# MSSRP-Temperature_System_beta_lite_2laye.net
KiCad netlist of a schematic drawn in EAGLE
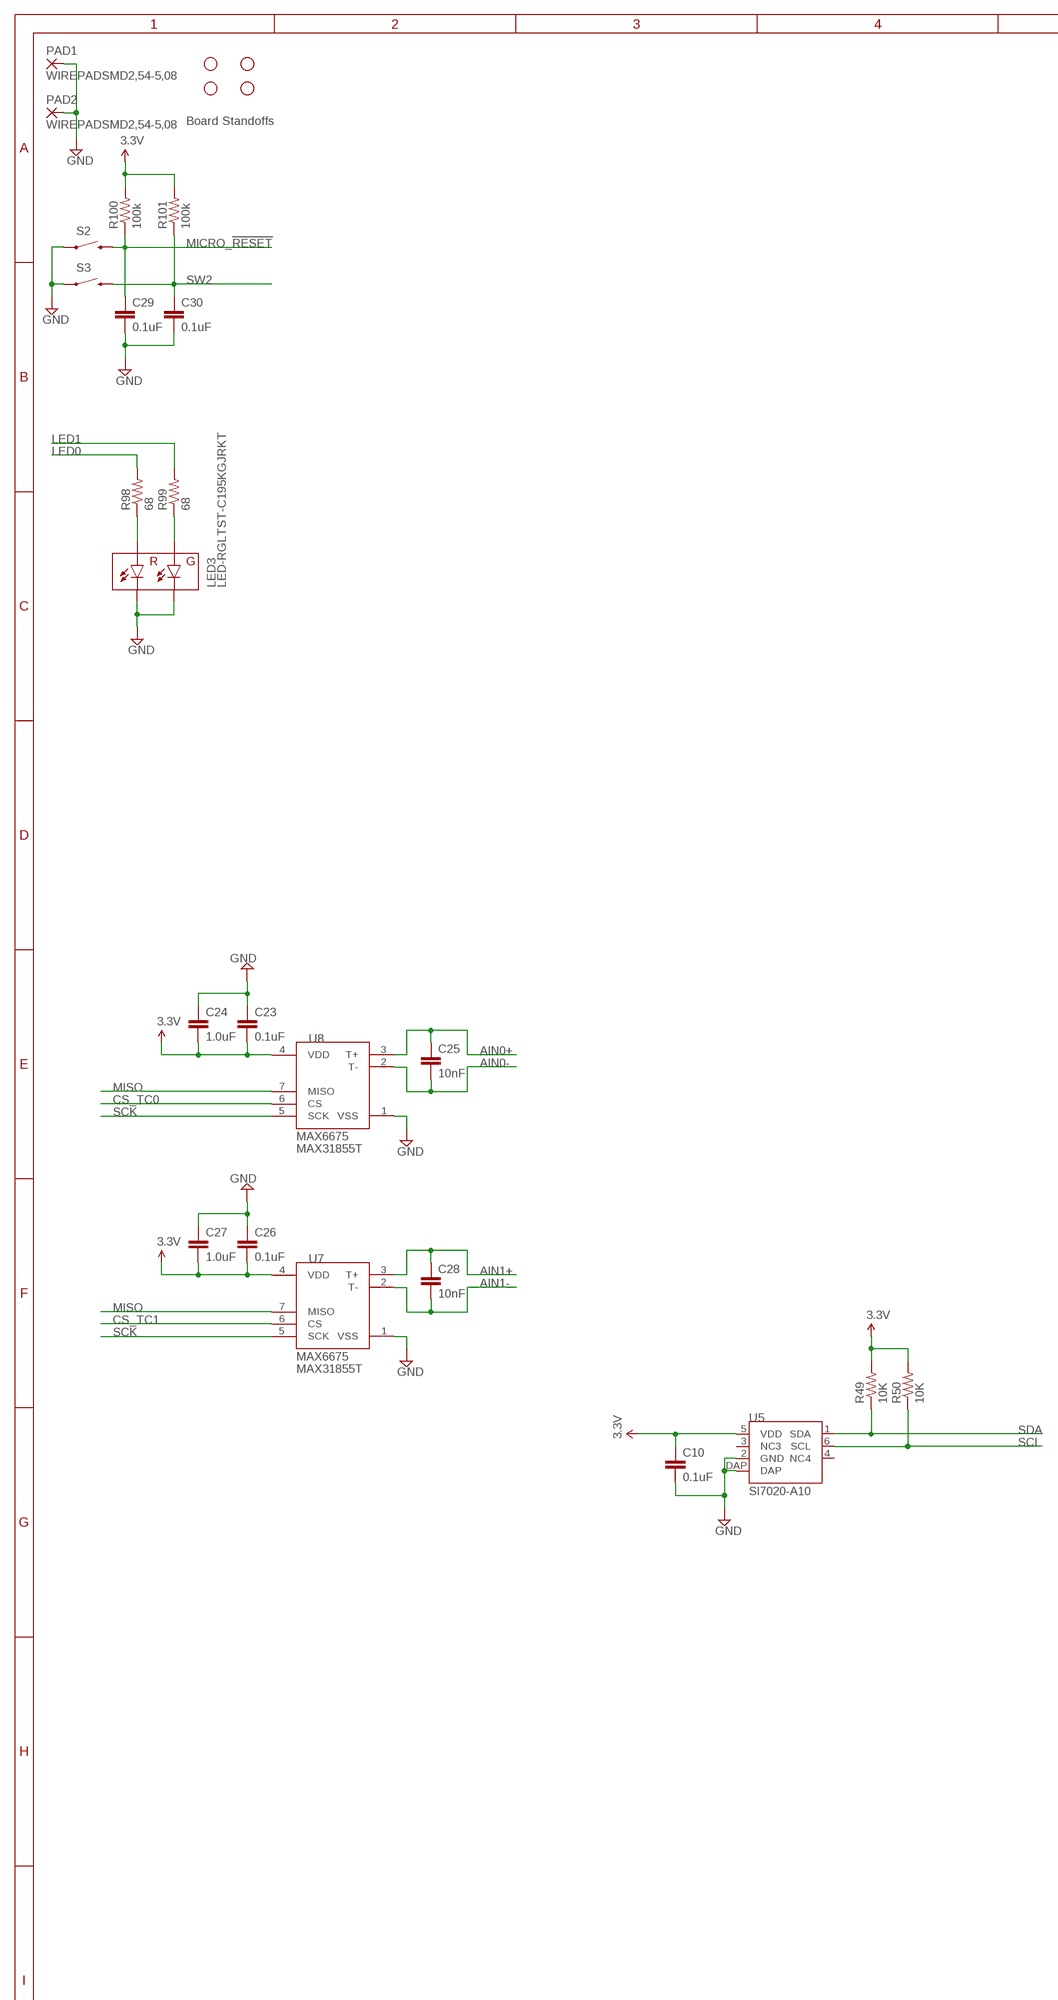
[diagram p0: schematic, sheet 1, part 1 of 2]
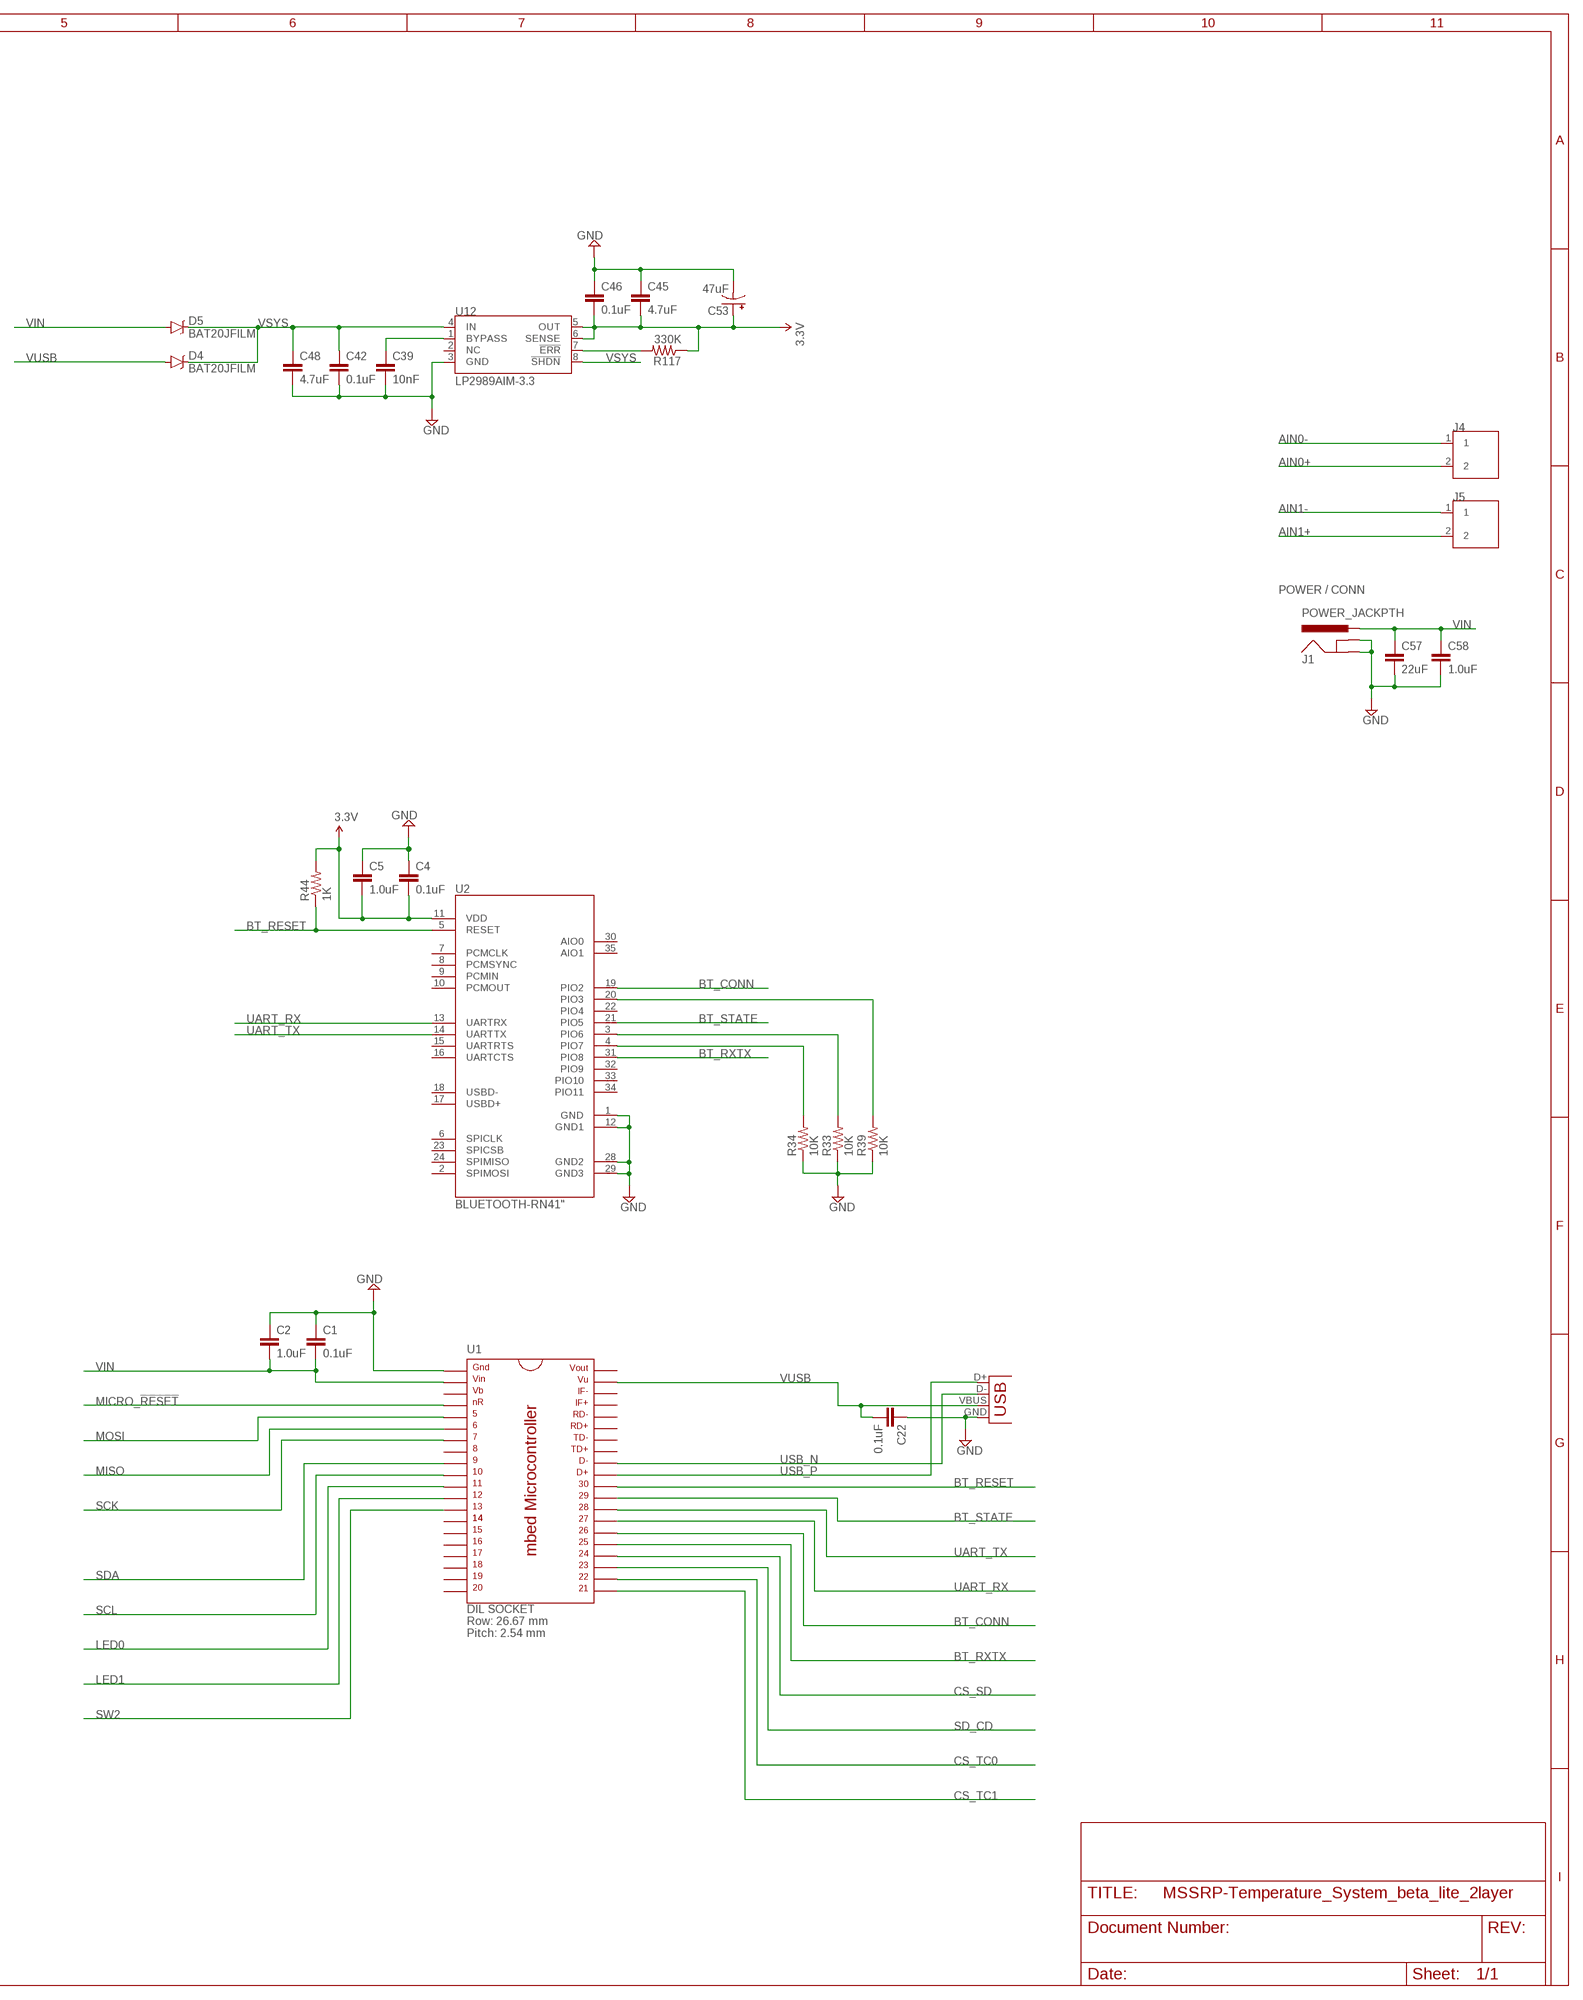
[diagram p1: schematic, sheet 1, part 2 of 2]

(export (version "E")
  (design (tool "Eeschema 10.0.6"))
  (components
    (comp (ref "C1")
      (value "0.1uF")
      (footprint "eagle-import:0603-CAP")
      (libsource (lib "eagle-import") (part "0.1UF-25V-5%(0603)"))
    )
    (comp (ref "C2")
      (value "1.0uF")
      (footprint "eagle-import:0603-CAP")
      (libsource (lib "eagle-import") (part "1.0UF-16V-10%(0603)"))
    )
    (comp (ref "C4")
      (value "0.1uF")
      (footprint "eagle-import:0603-CAP")
      (libsource (lib "eagle-import") (part "0.1UF-25V-5%(0603)"))
    )
    (comp (ref "C5")
      (value "1.0uF")
      (footprint "eagle-import:0603-CAP")
      (libsource (lib "eagle-import") (part "1.0UF-16V-10%(0603)"))
    )
    (comp (ref "C10")
      (value "0.1uF")
      (footprint "eagle-import:0603-CAP")
      (libsource (lib "eagle-import") (part "0.1UF-25V-5%(0603)"))
    )
    (comp (ref "C22")
      (value "0.1uF")
      (footprint "eagle-import:0603-CAP")
      (libsource (lib "eagle-import") (part "0.1UF-25V-5%(0603)"))
    )
    (comp (ref "C23")
      (value "0.1uF")
      (footprint "eagle-import:0603-CAP")
      (libsource (lib "eagle-import") (part "0.1UF-25V-5%(0603)"))
    )
    (comp (ref "C24")
      (value "1.0uF")
      (footprint "eagle-import:0603-CAP")
      (libsource (lib "eagle-import") (part "1.0UF-16V-10%(0603)"))
    )
    (comp (ref "C25")
      (value "10nF")
      (footprint "eagle-import:0603-CAP")
      (libsource (lib "eagle-import") (part "10NF/10000PF-50V-10%(0603)"))
    )
    (comp (ref "C26")
      (value "0.1uF")
      (footprint "eagle-import:0603-CAP")
      (libsource (lib "eagle-import") (part "0.1UF-25V-5%(0603)"))
    )
    (comp (ref "C27")
      (value "1.0uF")
      (footprint "eagle-import:0603-CAP")
      (libsource (lib "eagle-import") (part "1.0UF-16V-10%(0603)"))
    )
    (comp (ref "C28")
      (value "10nF")
      (footprint "eagle-import:0603-CAP")
      (libsource (lib "eagle-import") (part "10NF/10000PF-50V-10%(0603)"))
    )
    (comp (ref "C29")
      (value "0.1uF")
      (footprint "eagle-import:0603-CAP")
      (libsource (lib "eagle-import") (part "0.1UF-25V-5%(0603)"))
    )
    (comp (ref "C30")
      (value "0.1uF")
      (footprint "eagle-import:0603-CAP")
      (libsource (lib "eagle-import") (part "0.1UF-25V-5%(0603)"))
    )
    (comp (ref "C39")
      (value "10nF")
      (footprint "eagle-import:0603-CAP")
      (libsource (lib "eagle-import") (part "10NF/10000PF-50V-10%(0603)"))
    )
    (comp (ref "C42")
      (value "0.1uF")
      (footprint "eagle-import:0603-CAP")
      (libsource (lib "eagle-import") (part "0.1UF-25V-5%(0603)"))
    )
    (comp (ref "C45")
      (value "4.7uF")
      (footprint "eagle-import:0603-CAP")
      (libsource (lib "eagle-import") (part "4.7UF-6.3V-10%(0603)0603"))
    )
    (comp (ref "C46")
      (value "0.1uF")
      (footprint "eagle-import:0603-CAP")
      (libsource (lib "eagle-import") (part "0.1UF-25V-5%(0603)"))
    )
    (comp (ref "C48")
      (value "4.7uF")
      (footprint "eagle-import:0603-CAP")
      (libsource (lib "eagle-import") (part "4.7UF-6.3V-10%(0603)0603"))
    )
    (comp (ref "C53")
      (value "47uF")
      (footprint "eagle-import:EIA3528")
      (libsource (lib "eagle-import") (part "47UF-10V-10%(TANT)"))
    )
    (comp (ref "C57")
      (value "22uF")
      (footprint "eagle-import:1210")
      (libsource (lib "eagle-import") (part "22UF-16V-20%-(1210)"))
    )
    (comp (ref "C58")
      (value "1.0uF")
      (footprint "eagle-import:0603-CAP")
      (libsource (lib "eagle-import") (part "1.0UF-16V-10%(0603)"))
    )
    (comp (ref "D4")
      (value "BAT20JFILM")
      (footprint "eagle-import:SOD-323")
      (libsource (lib "eagle-import") (part "BAT20JFILM"))
    )
    (comp (ref "D5")
      (value "BAT20JFILM")
      (footprint "eagle-import:SOD-323")
      (libsource (lib "eagle-import") (part "BAT20JFILM"))
    )
    (comp (ref "J1")
      (value "POWER_JACKPTH")
      (footprint "eagle-import:POWER_JACK_PTH")
      (libsource (lib "eagle-import") (part "POWER_JACKPTH"))
    )
    (comp (ref "J4")
      (value "TE-2-TERMBLOCK")
      (footprint "eagle-import:TE-2-TERMBLOCK")
      (libsource (lib "eagle-import") (part "TE-2-TERMBLOCK"))
    )
    (comp (ref "J5")
      (value "TE-2-TERMBLOCK")
      (footprint "eagle-import:TE-2-TERMBLOCK")
      (libsource (lib "eagle-import") (part "TE-2-TERMBLOCK"))
    )
    (comp (ref "JP1")
      (value "USB-A-SMD")
      (footprint "eagle-import:USB-A-S-NOSILK-FEMALE")
      (libsource (lib "eagle-import") (part "USB-A-SMD"))
    )
    (comp (ref "LED3")
      (value "LED-RGLTST-C195KGJRKT")
      (footprint "eagle-import:LTST-C195KGJRKT")
      (libsource (lib "eagle-import") (part "LED-RGLTST-C195KGJRKT"))
    )
    (comp (ref "PAD1")
      (value "WIREPADSMD2,54-5,08")
      (footprint "eagle-import:SMD2,54-5,08")
      (libsource (lib "eagle-import") (part "WIREPADSMD2,54-5,08"))
    )
    (comp (ref "PAD2")
      (value "WIREPADSMD2,54-5,08")
      (footprint "eagle-import:SMD2,54-5,08")
      (libsource (lib "eagle-import") (part "WIREPADSMD2,54-5,08"))
    )
    (comp (ref "R33")
      (value "10K")
      (footprint "eagle-import:0603-RES")
      (libsource (lib "eagle-import") (part "10KOHM1/10W1%(0603)0603"))
    )
    (comp (ref "R34")
      (value "10K")
      (footprint "eagle-import:0603-RES")
      (libsource (lib "eagle-import") (part "10KOHM1/10W1%(0603)0603"))
    )
    (comp (ref "R39")
      (value "10K")
      (footprint "eagle-import:0603-RES")
      (libsource (lib "eagle-import") (part "10KOHM1/10W1%(0603)0603"))
    )
    (comp (ref "R44")
      (value "1K")
      (footprint "eagle-import:0603-RES")
      (libsource (lib "eagle-import") (part "1KOHM1/10W1%(0603)"))
    )
    (comp (ref "R49")
      (value "10K")
      (footprint "eagle-import:0603-RES")
      (libsource (lib "eagle-import") (part "10KOHM1/10W1%(0603)0603"))
    )
    (comp (ref "R50")
      (value "10K")
      (footprint "eagle-import:0603-RES")
      (libsource (lib "eagle-import") (part "10KOHM1/10W1%(0603)0603"))
    )
    (comp (ref "R98")
      (value "68")
      (footprint "eagle-import:0603-RES")
      (libsource (lib "eagle-import") (part "470OHM1/10W1%(0603)"))
    )
    (comp (ref "R99")
      (value "68")
      (footprint "eagle-import:0603-RES")
      (libsource (lib "eagle-import") (part "470OHM1/10W1%(0603)"))
    )
    (comp (ref "R100")
      (value "100k")
      (footprint "eagle-import:0603-RES")
      (libsource (lib "eagle-import") (part "100KOHM1/10W1%(0603)"))
    )
    (comp (ref "R101")
      (value "100k")
      (footprint "eagle-import:0603-RES")
      (libsource (lib "eagle-import") (part "100KOHM1/10W1%(0603)"))
    )
    (comp (ref "R117")
      (value "330K")
      (footprint "eagle-import:0603-RES")
      (libsource (lib "eagle-import") (part "330KOHM1/10W1%(0603)0603"))
    )
    (comp (ref "S2")
      (value "SWITCH-MOMENTARY-2-SMD-1101NE")
      (footprint "eagle-import:TACTILE-SWITCH-1101NE")
      (libsource (lib "eagle-import") (part "SWITCH-MOMENTARY-2-SMD-1101NE"))
    )
    (comp (ref "S3")
      (value "SWITCH-MOMENTARY-2-SMD-1101NE")
      (footprint "eagle-import:TACTILE-SWITCH-1101NE")
      (libsource (lib "eagle-import") (part "SWITCH-MOMENTARY-2-SMD-1101NE"))
    )
    (comp (ref "STANDOFF1")
      (value "STAND-OFF")
      (footprint "eagle-import:STAND-OFF")
      (libsource (lib "eagle-import") (part "STAND-OFF"))
    )
    (comp (ref "STANDOFF2")
      (value "STAND-OFF")
      (footprint "eagle-import:STAND-OFF")
      (libsource (lib "eagle-import") (part "STAND-OFF"))
    )
    (comp (ref "STANDOFF3")
      (value "STAND-OFF")
      (footprint "eagle-import:STAND-OFF")
      (libsource (lib "eagle-import") (part "STAND-OFF"))
    )
    (comp (ref "STANDOFF4")
      (value "STAND-OFF")
      (footprint "eagle-import:STAND-OFF")
      (libsource (lib "eagle-import") (part "STAND-OFF"))
    )
    (comp (ref "U1")
      (value "MBED")
      (footprint "eagle-import:DIL40_0.9")
      (libsource (lib "eagle-import") (part "MBED"))
    )
    (comp (ref "U2")
      (value "BLUETOOTH-RN41\"")
      (footprint "eagle-import:RN41")
      (libsource (lib "eagle-import") (part "BLUETOOTH-RN41{dblquote}"))
    )
    (comp (ref "U5")
      (value "SI7020-A10")
      (footprint "eagle-import:DFN6")
      (libsource (lib "eagle-import") (part "SI7020-A10"))
    )
    (comp (ref "U7")
      (value "MAX6675")
      (footprint "eagle-import:SO08-MAX6675")
      (libsource (lib "eagle-import") (part "MAX6675"))
    )
    (comp (ref "U8")
      (value "MAX6675")
      (footprint "eagle-import:SO08-MAX6675")
      (libsource (lib "eagle-import") (part "MAX6675"))
    )
    (comp (ref "U12")
      (value "LP2989AIM")
      (footprint "eagle-import:SOIC8")
      (libsource (lib "eagle-import") (part "LP2989AIM"))
    )
  )
  (nets
    (net (code "1") (name "/AIN0+") (class "Default")
      (node (ref "C25") (pin "1") (pinfunction "1_1") (pintype "passive"))
      (node (ref "J4") (pin "2") (pinfunction "2_2") (pintype "passive"))
      (node (ref "U8") (pin "3") (pinfunction "T+_3") (pintype "bidirectional"))
    )
    (net (code "2") (name "/AIN0-") (class "Default")
      (node (ref "C25") (pin "2") (pinfunction "2_2") (pintype "passive"))
      (node (ref "J4") (pin "1") (pinfunction "1_1") (pintype "passive"))
      (node (ref "U8") (pin "2") (pinfunction "T-_2") (pintype "bidirectional"))
    )
    (net (code "3") (name "/AIN1+") (class "Default")
      (node (ref "C28") (pin "1") (pinfunction "1_1") (pintype "passive"))
      (node (ref "J5") (pin "2") (pinfunction "2_2") (pintype "passive"))
      (node (ref "U7") (pin "3") (pinfunction "T+_3") (pintype "bidirectional"))
    )
    (net (code "4") (name "/AIN1-") (class "Default")
      (node (ref "C28") (pin "2") (pinfunction "2_2") (pintype "passive"))
      (node (ref "J5") (pin "1") (pinfunction "1_1") (pintype "passive"))
      (node (ref "U7") (pin "2") (pinfunction "T-_2") (pintype "bidirectional"))
    )
    (net (code "5") (name "/BT_CONN") (class "Default")
      (node (ref "U1") (pin "26") (pinfunction "P$26_26") (pintype "bidirectional"))
      (node (ref "U2") (pin "19") (pinfunction "PIO2_19") (pintype "bidirectional"))
    )
    (net (code "6") (name "/BT_RESET") (class "Default")
      (node (ref "R44") (pin "1") (pinfunction "1_1") (pintype "passive"))
      (node (ref "U1") (pin "30") (pinfunction "P$30_30") (pintype "bidirectional"))
      (node (ref "U2") (pin "5") (pinfunction "RESET_5") (pintype "bidirectional"))
    )
    (net (code "7") (name "/BT_RXTX") (class "Default")
      (node (ref "U1") (pin "25") (pinfunction "P$25_25") (pintype "bidirectional"))
      (node (ref "U2") (pin "31") (pinfunction "PIO8_31") (pintype "bidirectional"))
    )
    (net (code "8") (name "/BT_STATE") (class "Default")
      (node (ref "U1") (pin "29") (pinfunction "P$29_29") (pintype "bidirectional"))
      (node (ref "U2") (pin "21") (pinfunction "PIO5_21") (pintype "bidirectional"))
    )
    (net (code "9") (name "/CS_SD") (class "Default")
      (node (ref "U1") (pin "24") (pinfunction "P$24_24") (pintype "bidirectional"))
    )
    (net (code "10") (name "/CS_TC0") (class "Default")
      (node (ref "U1") (pin "22") (pinfunction "P$22_22") (pintype "bidirectional"))
      (node (ref "U8") (pin "6") (pinfunction "CS_6") (pintype "bidirectional"))
    )
    (net (code "11") (name "/CS_TC1") (class "Default")
      (node (ref "U1") (pin "21") (pinfunction "P$21_21") (pintype "bidirectional"))
      (node (ref "U7") (pin "6") (pinfunction "CS_6") (pintype "bidirectional"))
    )
    (net (code "12") (name "/LED0") (class "Default")
      (node (ref "R98") (pin "2") (pinfunction "2_2") (pintype "passive"))
      (node (ref "U1") (pin "11") (pinfunction "P$11_11") (pintype "bidirectional"))
    )
    (net (code "13") (name "/LED1") (class "Default")
      (node (ref "R99") (pin "2") (pinfunction "2_2") (pintype "passive"))
      (node (ref "U1") (pin "12") (pinfunction "P$12_12") (pintype "bidirectional"))
    )
    (net (code "14") (name "/MICRO_~{RESET}") (class "Default")
      (node (ref "C29") (pin "1") (pinfunction "1_1") (pintype "passive"))
      (node (ref "R100") (pin "1") (pinfunction "1_1") (pintype "passive"))
      (node (ref "S2") (pin "P$2") (pinfunction "2_P$2") (pintype "passive"))
      (node (ref "U1") (pin "4") (pinfunction "P$4_4") (pintype "bidirectional"))
    )
    (net (code "15") (name "/MISO") (class "Default")
      (node (ref "U1") (pin "6") (pinfunction "P$6_6") (pintype "bidirectional"))
      (node (ref "U7") (pin "7") (pinfunction "MISO_7") (pintype "bidirectional"))
      (node (ref "U8") (pin "7") (pinfunction "MISO_7") (pintype "bidirectional"))
    )
    (net (code "16") (name "/MOSI") (class "Default")
      (node (ref "U1") (pin "5") (pinfunction "P$5_5") (pintype "bidirectional"))
    )
    (net (code "17") (name "/SCK") (class "Default")
      (node (ref "U1") (pin "7") (pinfunction "P$7_7") (pintype "bidirectional"))
      (node (ref "U7") (pin "5") (pinfunction "SCK_5") (pintype "bidirectional"))
      (node (ref "U8") (pin "5") (pinfunction "SCK_5") (pintype "bidirectional"))
    )
    (net (code "18") (name "/SCL") (class "Default")
      (node (ref "R50") (pin "1") (pinfunction "1_1") (pintype "passive"))
      (node (ref "U1") (pin "10") (pinfunction "P$10_10") (pintype "bidirectional"))
      (node (ref "U5") (pin "6") (pinfunction "SCL_6") (pintype "bidirectional"))
    )
    (net (code "19") (name "/SDA") (class "Default")
      (node (ref "R49") (pin "1") (pinfunction "1_1") (pintype "passive"))
      (node (ref "U1") (pin "9") (pinfunction "P$9_9") (pintype "bidirectional"))
      (node (ref "U5") (pin "1") (pinfunction "SDA_1") (pintype "bidirectional"))
    )
    (net (code "20") (name "/SD_CD") (class "Default")
      (node (ref "U1") (pin "23") (pinfunction "P$23_23") (pintype "bidirectional"))
    )
    (net (code "21") (name "/SW2") (class "Default")
      (node (ref "C30") (pin "1") (pinfunction "1_1") (pintype "passive"))
      (node (ref "R101") (pin "1") (pinfunction "1_1") (pintype "passive"))
      (node (ref "S3") (pin "P$2") (pinfunction "2_P$2") (pintype "passive"))
      (node (ref "U1") (pin "13") (pinfunction "P$13_13") (pintype "bidirectional"))
    )
    (net (code "22") (name "/UART_RX") (class "Default")
      (node (ref "U1") (pin "27") (pinfunction "P$27_27") (pintype "bidirectional"))
      (node (ref "U2") (pin "13") (pinfunction "UARTRX_13") (pintype "bidirectional"))
    )
    (net (code "23") (name "/UART_TX") (class "Default")
      (node (ref "U1") (pin "28") (pinfunction "P$28_28") (pintype "bidirectional"))
      (node (ref "U2") (pin "14") (pinfunction "UARTTX_14") (pintype "bidirectional"))
    )
    (net (code "24") (name "/USB_N") (class "Default")
      (node (ref "JP1") (pin "D-") (pinfunction "D-_D-") (pintype "bidirectional"))
      (node (ref "U1") (pin "32") (pinfunction "P$32_32") (pintype "bidirectional"))
    )
    (net (code "25") (name "/USB_P") (class "Default")
      (node (ref "JP1") (pin "D+") (pinfunction "D+_D+") (pintype "bidirectional"))
      (node (ref "U1") (pin "31") (pinfunction "P$31_31") (pintype "bidirectional"))
    )
    (net (code "26") (name "/VIN") (class "Default")
      (node (ref "C1") (pin "2") (pinfunction "2_2") (pintype "passive"))
      (node (ref "C2") (pin "2") (pinfunction "2_2") (pintype "passive"))
      (node (ref "C57") (pin "1") (pinfunction "1_1") (pintype "passive"))
      (node (ref "C58") (pin "1") (pinfunction "1_1") (pintype "passive"))
      (node (ref "D5") (pin "A") (pinfunction "A_A") (pintype "passive"))
      (node (ref "J1") (pin "PWR") (pinfunction "PWR_PWR") (pintype "bidirectional"))
      (node (ref "U1") (pin "2") (pinfunction "P$2_2") (pintype "bidirectional"))
    )
    (net (code "27") (name "/VSYS") (class "Default")
      (node (ref "C42") (pin "1") (pinfunction "1_1") (pintype "passive"))
      (node (ref "C48") (pin "1") (pinfunction "1_1") (pintype "passive"))
      (node (ref "D4") (pin "C") (pinfunction "C_C") (pintype "passive"))
      (node (ref "D5") (pin "C") (pinfunction "C_C") (pintype "passive"))
      (node (ref "U12") (pin "4") (pinfunction "IN_4") (pintype "power_in"))
      (node (ref "U12") (pin "8") (pinfunction "~{SHDN}_8") (pintype "input"))
    )
    (net (code "28") (name "/VUSB") (class "Default")
      (node (ref "C22") (pin "2") (pinfunction "2_2") (pintype "passive"))
      (node (ref "D4") (pin "A") (pinfunction "A_A") (pintype "passive"))
      (node (ref "JP1") (pin "VBUS") (pinfunction "VBUS_VBUS") (pintype "bidirectional"))
      (node (ref "U1") (pin "39") (pinfunction "P$39_39") (pintype "bidirectional"))
    )
    (net (code "29") (name "3.3V") (class "Default")
      (node (ref "C10") (pin "1") (pinfunction "1_1") (pintype "passive"))
      (node (ref "C23") (pin "2") (pinfunction "2_2") (pintype "passive"))
      (node (ref "C24") (pin "2") (pinfunction "2_2") (pintype "passive"))
      (node (ref "C26") (pin "2") (pinfunction "2_2") (pintype "passive"))
      (node (ref "C27") (pin "2") (pinfunction "2_2") (pintype "passive"))
      (node (ref "C4") (pin "2") (pinfunction "2_2") (pintype "passive"))
      (node (ref "C45") (pin "2") (pinfunction "2_2") (pintype "passive"))
      (node (ref "C46") (pin "2") (pinfunction "2_2") (pintype "passive"))
      (node (ref "C5") (pin "2") (pinfunction "2_2") (pintype "passive"))
      (node (ref "C53") (pin "A") (pinfunction "+_A") (pintype "passive"))
      (node (ref "R100") (pin "2") (pinfunction "2_2") (pintype "passive"))
      (node (ref "R101") (pin "2") (pinfunction "2_2") (pintype "passive"))
      (node (ref "R117") (pin "1") (pinfunction "1_1") (pintype "passive"))
      (node (ref "R44") (pin "2") (pinfunction "2_2") (pintype "passive"))
      (node (ref "R49") (pin "2") (pinfunction "2_2") (pintype "passive"))
      (node (ref "R50") (pin "2") (pinfunction "2_2") (pintype "passive"))
      (node (ref "U12") (pin "5") (pinfunction "OUT_5") (pintype "power_in"))
      (node (ref "U12") (pin "6") (pinfunction "SENSE_6") (pintype "passive"))
      (node (ref "U2") (pin "11") (pinfunction "VDD_11") (pintype "bidirectional"))
      (node (ref "U5") (pin "5") (pinfunction "VDD_5") (pintype "power_in"))
      (node (ref "U7") (pin "4") (pinfunction "VDD_4") (pintype "bidirectional"))
      (node (ref "U8") (pin "4") (pinfunction "VDD_4") (pintype "bidirectional"))
    )
    (net (code "30") (name "GND") (class "Default")
      (node (ref "C1") (pin "1") (pinfunction "1_1") (pintype "passive"))
      (node (ref "C10") (pin "2") (pinfunction "2_2") (pintype "passive"))
      (node (ref "C2") (pin "1") (pinfunction "1_1") (pintype "passive"))
      (node (ref "C22") (pin "1") (pinfunction "1_1") (pintype "passive"))
      (node (ref "C23") (pin "1") (pinfunction "1_1") (pintype "passive"))
      (node (ref "C24") (pin "1") (pinfunction "1_1") (pintype "passive"))
      (node (ref "C26") (pin "1") (pinfunction "1_1") (pintype "passive"))
      (node (ref "C27") (pin "1") (pinfunction "1_1") (pintype "passive"))
      (node (ref "C29") (pin "2") (pinfunction "2_2") (pintype "passive"))
      (node (ref "C30") (pin "2") (pinfunction "2_2") (pintype "passive"))
      (node (ref "C39") (pin "2") (pinfunction "2_2") (pintype "passive"))
      (node (ref "C4") (pin "1") (pinfunction "1_1") (pintype "passive"))
      (node (ref "C42") (pin "2") (pinfunction "2_2") (pintype "passive"))
      (node (ref "C45") (pin "1") (pinfunction "1_1") (pintype "passive"))
      (node (ref "C46") (pin "1") (pinfunction "1_1") (pintype "passive"))
      (node (ref "C48") (pin "2") (pinfunction "2_2") (pintype "passive"))
      (node (ref "C5") (pin "1") (pinfunction "1_1") (pintype "passive"))
      (node (ref "C53") (pin "C") (pinfunction "-_C") (pintype "passive"))
      (node (ref "C57") (pin "2") (pinfunction "2_2") (pintype "passive"))
      (node (ref "C58") (pin "2") (pinfunction "2_2") (pintype "passive"))
      (node (ref "J1") (pin "GND") (pinfunction "GND_GND") (pintype "bidirectional"))
      (node (ref "J1") (pin "GNDBREAK") (pinfunction "GNDBREAK_GNDBREAK") (pintype "bidirectional"))
      (node (ref "JP1") (pin "GND") (pinfunction "GND_GND") (pintype "bidirectional"))
      (node (ref "LED3") (pin "P$3") (pinfunction "GC_P$3") (pintype "passive"))
      (node (ref "LED3") (pin "P$4") (pinfunction "RC_P$4") (pintype "passive"))
      (node (ref "PAD1") (pin "1") (pinfunction "P_1") (pintype "passive"))
      (node (ref "PAD2") (pin "1") (pinfunction "P_1") (pintype "passive"))
      (node (ref "R33") (pin "1") (pinfunction "1_1") (pintype "passive"))
      (node (ref "R34") (pin "1") (pinfunction "1_1") (pintype "passive"))
      (node (ref "R39") (pin "1") (pinfunction "1_1") (pintype "passive"))
      (node (ref "S2") (pin "P$1") (pinfunction "1_P$1") (pintype "passive"))
      (node (ref "S3") (pin "P$1") (pinfunction "1_P$1") (pintype "passive"))
      (node (ref "U1") (pin "1") (pinfunction "P$1_1") (pintype "bidirectional"))
      (node (ref "U12") (pin "3") (pinfunction "GND_3") (pintype "power_in"))
      (node (ref "U2") (pin "1") (pinfunction "GND_1") (pintype "bidirectional"))
      (node (ref "U2") (pin "12") (pinfunction "GND1_12") (pintype "bidirectional"))
      (node (ref "U2") (pin "28") (pinfunction "GND2_28") (pintype "bidirectional"))
      (node (ref "U2") (pin "29") (pinfunction "GND3_29") (pintype "bidirectional"))
      (node (ref "U5") (pin "2") (pinfunction "GND_2") (pintype "power_in"))
      (node (ref "U5") (pin "DAP") (pinfunction "DAP_DAP") (pintype "bidirectional"))
      (node (ref "U7") (pin "1") (pinfunction "VSS_1") (pintype "bidirectional"))
      (node (ref "U8") (pin "1") (pinfunction "VSS_1") (pintype "bidirectional"))
    )
    (net (code "31") (name "Net-(LED3-GA)") (class "Default")
      (node (ref "LED3") (pin "P$1") (pinfunction "GA_P$1") (pintype "passive"))
      (node (ref "R99") (pin "1") (pinfunction "1_1") (pintype "passive"))
    )
    (net (code "32") (name "Net-(LED3-RA)") (class "Default")
      (node (ref "LED3") (pin "P$2") (pinfunction "RA_P$2") (pintype "passive"))
      (node (ref "R98") (pin "1") (pinfunction "1_1") (pintype "passive"))
    )
    (net (code "33") (name "Net-(U2-PIO3)") (class "Default")
      (node (ref "R39") (pin "2") (pinfunction "2_2") (pintype "passive"))
      (node (ref "U2") (pin "20") (pinfunction "PIO3_20") (pintype "bidirectional"))
    )
    (net (code "34") (name "Net-(U2-PIO6)") (class "Default")
      (node (ref "R33") (pin "2") (pinfunction "2_2") (pintype "passive"))
      (node (ref "U2") (pin "3") (pinfunction "PIO6_3") (pintype "bidirectional"))
    )
    (net (code "35") (name "Net-(U2-PIO7)") (class "Default")
      (node (ref "R34") (pin "2") (pinfunction "2_2") (pintype "passive"))
      (node (ref "U2") (pin "4") (pinfunction "PIO7_4") (pintype "bidirectional"))
    )
    (net (code "36") (name "Net-(U12-BYPASS)") (class "Default")
      (node (ref "C39") (pin "1") (pinfunction "1_1") (pintype "passive"))
      (node (ref "U12") (pin "1") (pinfunction "BYPASS_1") (pintype "passive"))
    )
    (net (code "37") (name "Net-(U12-~{ERR})") (class "Default")
      (node (ref "R117") (pin "2") (pinfunction "2_2") (pintype "passive"))
      (node (ref "U12") (pin "7") (pinfunction "~{ERR}_7") (pintype "output"))
    )
    (net (code "38") (name "unconnected-(U1-P$3-Pad3)") (class "Default")
      (node (ref "U1") (pin "3") (pinfunction "P$3_3") (pintype "bidirectional"))
    )
    (net (code "39") (name "unconnected-(U1-P$8-Pad8)") (class "Default")
      (node (ref "U1") (pin "8") (pinfunction "P$8_8") (pintype "bidirectional"))
    )
    (net (code "40") (name "unconnected-(U1-P$14-Pad14)") (class "Default")
      (node (ref "U1") (pin "14") (pinfunction "P$14_14") (pintype "bidirectional"))
    )
    (net (code "41") (name "unconnected-(U1-P$15-Pad15)") (class "Default")
      (node (ref "U1") (pin "15") (pinfunction "P$15_15") (pintype "bidirectional"))
    )
    (net (code "42") (name "unconnected-(U1-P$16-Pad16)") (class "Default")
      (node (ref "U1") (pin "16") (pinfunction "P$16_16") (pintype "bidirectional"))
    )
    (net (code "43") (name "unconnected-(U1-P$17-Pad17)") (class "Default")
      (node (ref "U1") (pin "17") (pinfunction "P$17_17") (pintype "bidirectional"))
    )
    (net (code "44") (name "unconnected-(U1-P$18-Pad18)") (class "Default")
      (node (ref "U1") (pin "18") (pinfunction "P$18_18") (pintype "bidirectional"))
    )
    (net (code "45") (name "unconnected-(U1-P$19-Pad19)") (class "Default")
      (node (ref "U1") (pin "19") (pinfunction "P$19_19") (pintype "bidirectional"))
    )
    (net (code "46") (name "unconnected-(U1-P$20-Pad20)") (class "Default")
      (node (ref "U1") (pin "20") (pinfunction "P$20_20") (pintype "bidirectional"))
    )
    (net (code "47") (name "unconnected-(U1-P$33-Pad33)") (class "Default")
      (node (ref "U1") (pin "33") (pinfunction "P$33_33") (pintype "bidirectional"))
    )
    (net (code "48") (name "unconnected-(U1-P$34-Pad34)") (class "Default")
      (node (ref "U1") (pin "34") (pinfunction "P$34_34") (pintype "bidirectional"))
    )
    (net (code "49") (name "unconnected-(U1-P$35-Pad35)") (class "Default")
      (node (ref "U1") (pin "35") (pinfunction "P$35_35") (pintype "bidirectional"))
    )
    (net (code "50") (name "unconnected-(U1-P$36-Pad36)") (class "Default")
      (node (ref "U1") (pin "36") (pinfunction "P$36_36") (pintype "bidirectional"))
    )
    (net (code "51") (name "unconnected-(U1-P$37-Pad37)") (class "Default")
      (node (ref "U1") (pin "37") (pinfunction "P$37_37") (pintype "bidirectional"))
    )
    (net (code "52") (name "unconnected-(U1-P$38-Pad38)") (class "Default")
      (node (ref "U1") (pin "38") (pinfunction "P$38_38") (pintype "bidirectional"))
    )
    (net (code "53") (name "unconnected-(U1-P$40-Pad40)") (class "Default")
      (node (ref "U1") (pin "40") (pinfunction "P$40_40") (pintype "bidirectional"))
    )
    (net (code "54") (name "unconnected-(U2-AIO0-Pad30)") (class "Default")
      (node (ref "U2") (pin "30") (pinfunction "AIO0_30") (pintype "bidirectional"))
    )
    (net (code "55") (name "unconnected-(U2-AIO1-Pad35)") (class "Default")
      (node (ref "U2") (pin "35") (pinfunction "AIO1_35") (pintype "bidirectional"))
    )
    (net (code "56") (name "unconnected-(U2-PCMCLK-Pad7)") (class "Default")
      (node (ref "U2") (pin "7") (pinfunction "PCMCLK_7") (pintype "bidirectional"))
    )
    (net (code "57") (name "unconnected-(U2-PCMIN-Pad9)") (class "Default")
      (node (ref "U2") (pin "9") (pinfunction "PCMIN_9") (pintype "bidirectional"))
    )
    (net (code "58") (name "unconnected-(U2-PCMOUT-Pad10)") (class "Default")
      (node (ref "U2") (pin "10") (pinfunction "PCMOUT_10") (pintype "bidirectional"))
    )
    (net (code "59") (name "unconnected-(U2-PCMSYNC-Pad8)") (class "Default")
      (node (ref "U2") (pin "8") (pinfunction "PCMSYNC_8") (pintype "bidirectional"))
    )
    (net (code "60") (name "unconnected-(U2-PIO4-Pad22)") (class "Default")
      (node (ref "U2") (pin "22") (pinfunction "PIO4_22") (pintype "bidirectional"))
    )
    (net (code "61") (name "unconnected-(U2-PIO9-Pad32)") (class "Default")
      (node (ref "U2") (pin "32") (pinfunction "PIO9_32") (pintype "bidirectional"))
    )
    (net (code "62") (name "unconnected-(U2-PIO10-Pad33)") (class "Default")
      (node (ref "U2") (pin "33") (pinfunction "PIO10_33") (pintype "bidirectional"))
    )
    (net (code "63") (name "unconnected-(U2-PIO11-Pad34)") (class "Default")
      (node (ref "U2") (pin "34") (pinfunction "PIO11_34") (pintype "bidirectional"))
    )
    (net (code "64") (name "unconnected-(U2-SPICLK-Pad6)") (class "Default")
      (node (ref "U2") (pin "6") (pinfunction "SPICLK_6") (pintype "bidirectional"))
    )
    (net (code "65") (name "unconnected-(U2-SPICSB-Pad23)") (class "Default")
      (node (ref "U2") (pin "23") (pinfunction "SPICSB_23") (pintype "bidirectional"))
    )
    (net (code "66") (name "unconnected-(U2-SPIMISO-Pad24)") (class "Default")
      (node (ref "U2") (pin "24") (pinfunction "SPIMISO_24") (pintype "bidirectional"))
    )
    (net (code "67") (name "unconnected-(U2-SPIMOSI-Pad2)") (class "Default")
      (node (ref "U2") (pin "2") (pinfunction "SPIMOSI_2") (pintype "bidirectional"))
    )
    (net (code "68") (name "unconnected-(U2-UARTCTS-Pad16)") (class "Default")
      (node (ref "U2") (pin "16") (pinfunction "UARTCTS_16") (pintype "bidirectional"))
    )
    (net (code "69") (name "unconnected-(U2-UARTRTS-Pad15)") (class "Default")
      (node (ref "U2") (pin "15") (pinfunction "UARTRTS_15") (pintype "bidirectional"))
    )
    (net (code "70") (name "unconnected-(U2-USBD+-Pad17)") (class "Default")
      (node (ref "U2") (pin "17") (pinfunction "USBD+_17") (pintype "bidirectional"))
    )
    (net (code "71") (name "unconnected-(U2-USBD--Pad18)") (class "Default")
      (node (ref "U2") (pin "18") (pinfunction "USBD-_18") (pintype "bidirectional"))
    )
    (net (code "72") (name "unconnected-(U5-NC3-Pad3)") (class "Default")
      (node (ref "U5") (pin "3") (pinfunction "NC3_3") (pintype "no_connect"))
    )
    (net (code "73") (name "unconnected-(U5-NC4-Pad4)") (class "Default")
      (node (ref "U5") (pin "4") (pinfunction "NC4_4") (pintype "no_connect"))
    )
    (net (code "74") (name "unconnected-(U12-NC-Pad2)") (class "Default")
      (node (ref "U12") (pin "2") (pinfunction "NC_2") (pintype "bidirectional"))
    )
  )
)
